# FPGA_-_POWER.net
KiCad netlist of a schematic drawn in Altium Designer
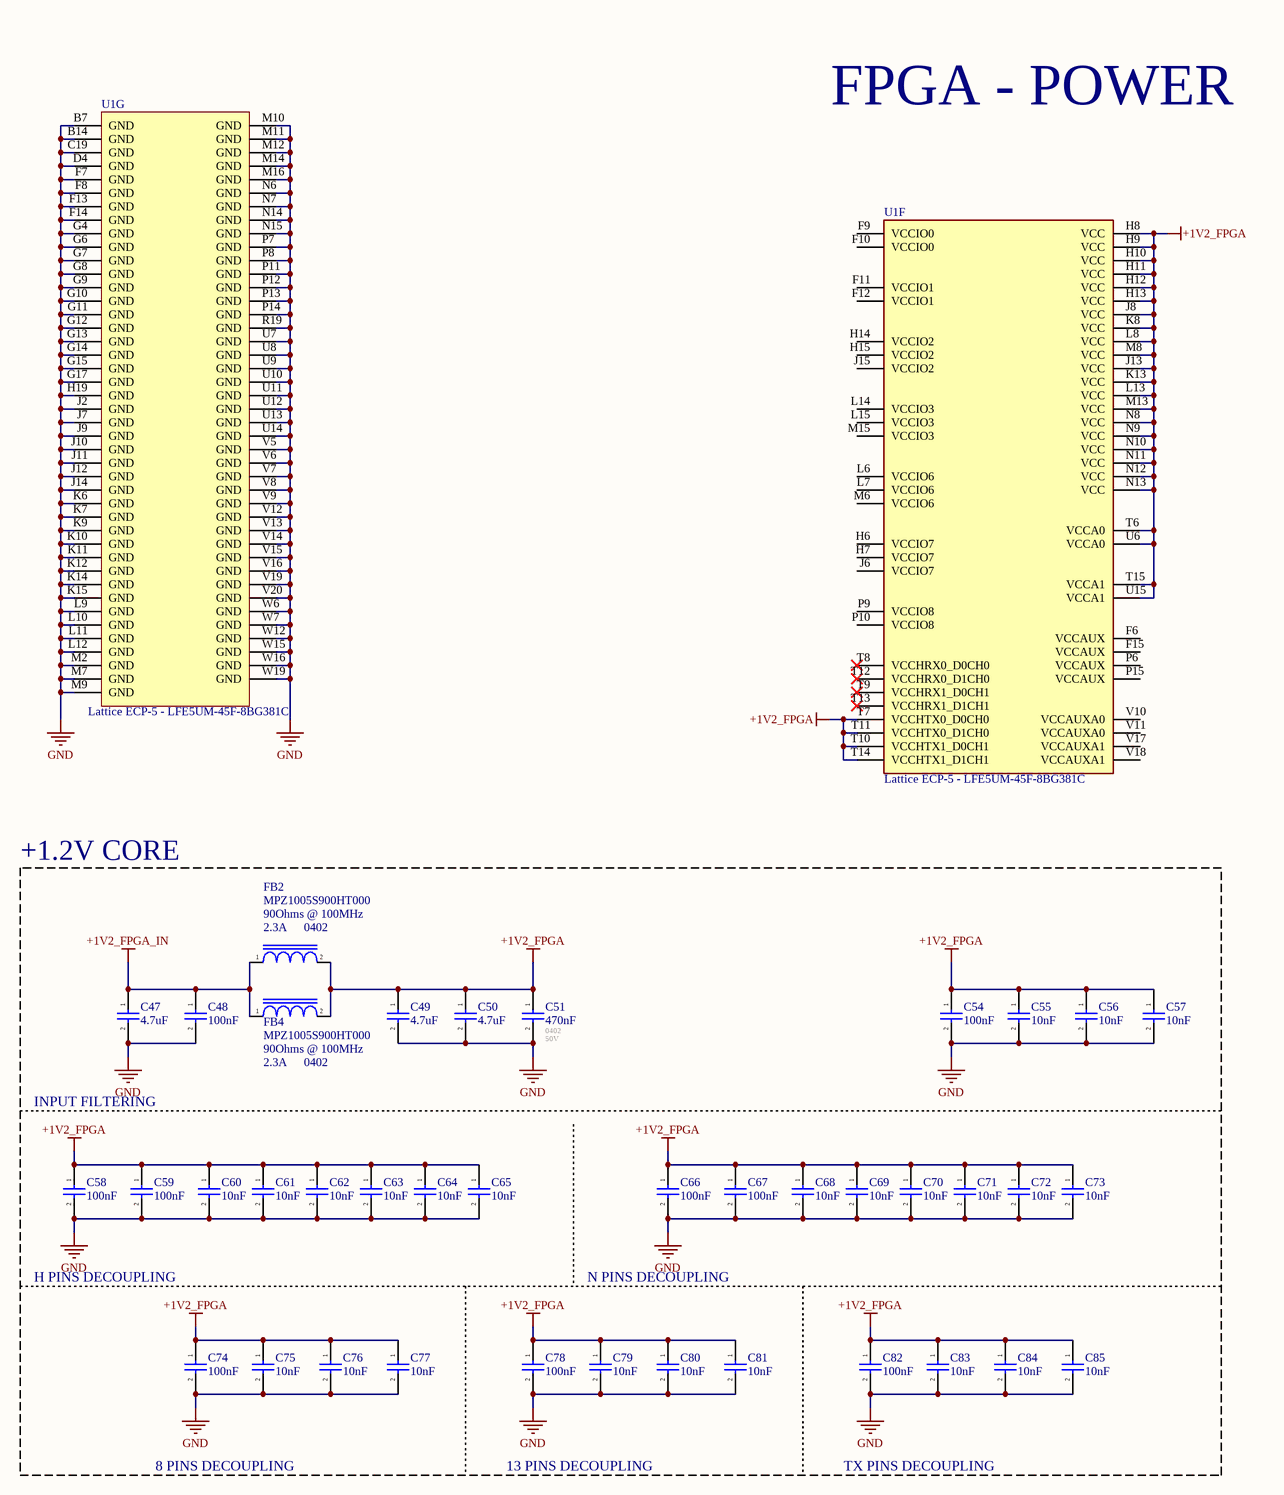
[diagram p0: FPGA - POWER.SchDoc]

(export (version "E")
  (design (tool "Eeschema 10.0.6"))
  (components
    (comp (ref "C47")
      (value "4.7uF")
      (footprint "CAP_0805")
      (description "Generic SMT Ceramic Capacitor")
      (libsource (lib "Symbols") (part "CAP_CER"))
    )
    (comp (ref "C48")
      (value "100nF")
      (footprint "CAP_0402")
      (description "Generic SMT Ceramic Capacitor")
      (libsource (lib "Symbols") (part "CAP_CER"))
    )
    (comp (ref "C49")
      (value "4.7uF")
      (footprint "CAP_0805")
      (description "Generic SMT Ceramic Capacitor")
      (libsource (lib "Symbols") (part "CAP_CER"))
    )
    (comp (ref "C50")
      (value "4.7uF")
      (footprint "CAP_0805")
      (description "Generic SMT Ceramic Capacitor")
      (libsource (lib "Symbols") (part "CAP_CER"))
    )
    (comp (ref "C51")
      (value "470nF")
      (footprint "0402")
      (description "Generic SMT Ceramic Capacitor")
      (fields (field (name "VOLTAGE - RATED") "50V"))
      (libsource (lib "Symbols") (part "CAP_CER"))
    )
    (comp (ref "C54")
      (value "100nF")
      (footprint "CAP_0402")
      (description "Generic SMT Ceramic Capacitor")
      (libsource (lib "Symbols") (part "CAP_CER"))
    )
    (comp (ref "C55")
      (value "10nF")
      (footprint "CAP_0201")
      (description "Generic SMT Ceramic Capacitor")
      (libsource (lib "Symbols") (part "CAP_CER"))
    )
    (comp (ref "C56")
      (value "10nF")
      (footprint "CAP_0201")
      (description "Generic SMT Ceramic Capacitor")
      (libsource (lib "Symbols") (part "CAP_CER"))
    )
    (comp (ref "C57")
      (value "10nF")
      (footprint "CAP_0201")
      (description "Generic SMT Ceramic Capacitor")
      (libsource (lib "Symbols") (part "CAP_CER"))
    )
    (comp (ref "C58")
      (value "100nF")
      (footprint "CAP_0402")
      (description "Generic SMT Ceramic Capacitor")
      (libsource (lib "Symbols") (part "CAP_CER"))
    )
    (comp (ref "C59")
      (value "100nF")
      (footprint "CAP_0402")
      (description "Generic SMT Ceramic Capacitor")
      (libsource (lib "Symbols") (part "CAP_CER"))
    )
    (comp (ref "C60")
      (value "10nF")
      (footprint "CAP_0201")
      (description "Generic SMT Ceramic Capacitor")
      (libsource (lib "Symbols") (part "CAP_CER"))
    )
    (comp (ref "C61")
      (value "10nF")
      (footprint "CAP_0201")
      (description "Generic SMT Ceramic Capacitor")
      (libsource (lib "Symbols") (part "CAP_CER"))
    )
    (comp (ref "C62")
      (value "10nF")
      (footprint "CAP_0201")
      (description "Generic SMT Ceramic Capacitor")
      (libsource (lib "Symbols") (part "CAP_CER"))
    )
    (comp (ref "C63")
      (value "10nF")
      (footprint "CAP_0201")
      (description "Generic SMT Ceramic Capacitor")
      (libsource (lib "Symbols") (part "CAP_CER"))
    )
    (comp (ref "C64")
      (value "10nF")
      (footprint "CAP_0201")
      (description "Generic SMT Ceramic Capacitor")
      (libsource (lib "Symbols") (part "CAP_CER"))
    )
    (comp (ref "C65")
      (value "10nF")
      (footprint "CAP_0201")
      (description "Generic SMT Ceramic Capacitor")
      (libsource (lib "Symbols") (part "CAP_CER"))
    )
    (comp (ref "C66")
      (value "100nF")
      (footprint "CAP_0402")
      (description "Generic SMT Ceramic Capacitor")
      (libsource (lib "Symbols") (part "CAP_CER"))
    )
    (comp (ref "C67")
      (value "100nF")
      (footprint "CAP_0402")
      (description "Generic SMT Ceramic Capacitor")
      (libsource (lib "Symbols") (part "CAP_CER"))
    )
    (comp (ref "C68")
      (value "10nF")
      (footprint "CAP_0201")
      (description "Generic SMT Ceramic Capacitor")
      (libsource (lib "Symbols") (part "CAP_CER"))
    )
    (comp (ref "C69")
      (value "10nF")
      (footprint "CAP_0201")
      (description "Generic SMT Ceramic Capacitor")
      (libsource (lib "Symbols") (part "CAP_CER"))
    )
    (comp (ref "C70")
      (value "10nF")
      (footprint "CAP_0201")
      (description "Generic SMT Ceramic Capacitor")
      (libsource (lib "Symbols") (part "CAP_CER"))
    )
    (comp (ref "C71")
      (value "10nF")
      (footprint "CAP_0201")
      (description "Generic SMT Ceramic Capacitor")
      (libsource (lib "Symbols") (part "CAP_CER"))
    )
    (comp (ref "C72")
      (value "10nF")
      (footprint "CAP_0201")
      (description "Generic SMT Ceramic Capacitor")
      (libsource (lib "Symbols") (part "CAP_CER"))
    )
    (comp (ref "C73")
      (value "10nF")
      (footprint "CAP_0201")
      (description "Generic SMT Ceramic Capacitor")
      (libsource (lib "Symbols") (part "CAP_CER"))
    )
    (comp (ref "C74")
      (value "100nF")
      (footprint "CAP_0402")
      (description "Generic SMT Ceramic Capacitor")
      (libsource (lib "Symbols") (part "CAP_CER"))
    )
    (comp (ref "C75")
      (value "10nF")
      (footprint "CAP_0201")
      (description "Generic SMT Ceramic Capacitor")
      (libsource (lib "Symbols") (part "CAP_CER"))
    )
    (comp (ref "C76")
      (value "10nF")
      (footprint "CAP_0201")
      (description "Generic SMT Ceramic Capacitor")
      (libsource (lib "Symbols") (part "CAP_CER"))
    )
    (comp (ref "C77")
      (value "10nF")
      (footprint "CAP_0201")
      (description "Generic SMT Ceramic Capacitor")
      (libsource (lib "Symbols") (part "CAP_CER"))
    )
    (comp (ref "C78")
      (value "100nF")
      (footprint "CAP_0402")
      (description "Generic SMT Ceramic Capacitor")
      (libsource (lib "Symbols") (part "CAP_CER"))
    )
    (comp (ref "C79")
      (value "10nF")
      (footprint "CAP_0201")
      (description "Generic SMT Ceramic Capacitor")
      (libsource (lib "Symbols") (part "CAP_CER"))
    )
    (comp (ref "C80")
      (value "10nF")
      (footprint "CAP_0201")
      (description "Generic SMT Ceramic Capacitor")
      (libsource (lib "Symbols") (part "CAP_CER"))
    )
    (comp (ref "C81")
      (value "10nF")
      (footprint "CAP_0201")
      (description "Generic SMT Ceramic Capacitor")
      (libsource (lib "Symbols") (part "CAP_CER"))
    )
    (comp (ref "C82")
      (value "100nF")
      (footprint "CAP_0402")
      (description "Generic SMT Ceramic Capacitor")
      (libsource (lib "Symbols") (part "CAP_CER"))
    )
    (comp (ref "C83")
      (value "10nF")
      (footprint "CAP_0201")
      (description "Generic SMT Ceramic Capacitor")
      (libsource (lib "Symbols") (part "CAP_CER"))
    )
    (comp (ref "C84")
      (value "10nF")
      (footprint "CAP_0201")
      (description "Generic SMT Ceramic Capacitor")
      (libsource (lib "Symbols") (part "CAP_CER"))
    )
    (comp (ref "C85")
      (value "10nF")
      (footprint "CAP_0201")
      (description "Generic SMT Ceramic Capacitor")
      (libsource (lib "Symbols") (part "CAP_CER"))
    )
    (comp (ref "FB2")
      (value "MPZ1005S900HT000")
      (footprint "IND_0402")
      (description "90 Ohms @ 100 MHz 1 Power Line Ferrite Bead 0402 (1005 Metric) 2.3A 38mOhm")
      (fields
        (field (name "IMPEDANCE @ FREQ") "90Ohms @ 100MHz")
        (field (name "PACKAGE / CASE") "0402")
        (field (name "CURRENT RATING") "2.3A")
      )
      (libsource (lib "CryptLib") (part "IND_MPZ1005S900HT000"))
    )
    (comp (ref "FB4")
      (value "MPZ1005S900HT000")
      (footprint "IND_0402")
      (description "90 Ohms @ 100 MHz 1 Power Line Ferrite Bead 0402 (1005 Metric) 2.3A 38mOhm")
      (fields
        (field (name "IMPEDANCE @ FREQ") "90Ohms @ 100MHz")
        (field (name "PACKAGE / CASE") "0402")
        (field (name "CURRENT RATING") "2.3A")
      )
      (libsource (lib "CryptLib") (part "IND_MPZ1005S900HT000"))
    )
    (comp (ref "U1")
      (value "Lattice ECP-5 - LFE5UM-45F-8BG381C")
      (footprint "CABGA-381")
      (description "IC FPGA 203 I/O 381CABGA")
      (fields (field (name "MFR") "Lattice Semiconductors"))
      (libsource (lib "CryptLib") (part "IC_LFE5UM-45F-8BG381C"))
    )
  )
  (nets
    (net (code "1") (name "+1V2_FPGA") (class "Default")
      (node (ref "C49") (pin "1") (pinfunction "1_1") (pintype "passive"))
      (node (ref "C50") (pin "1") (pinfunction "1_1") (pintype "passive"))
      (node (ref "C51") (pin "1") (pinfunction "1_1") (pintype "passive"))
      (node (ref "C54") (pin "1") (pinfunction "1_1") (pintype "passive"))
      (node (ref "C55") (pin "1") (pinfunction "1_1") (pintype "passive"))
      (node (ref "C56") (pin "1") (pinfunction "1_1") (pintype "passive"))
      (node (ref "C57") (pin "1") (pinfunction "1_1") (pintype "passive"))
      (node (ref "C58") (pin "1") (pinfunction "1_1") (pintype "passive"))
      (node (ref "C59") (pin "1") (pinfunction "1_1") (pintype "passive"))
      (node (ref "C60") (pin "1") (pinfunction "1_1") (pintype "passive"))
      (node (ref "C61") (pin "1") (pinfunction "1_1") (pintype "passive"))
      (node (ref "C62") (pin "1") (pinfunction "1_1") (pintype "passive"))
      (node (ref "C63") (pin "1") (pinfunction "1_1") (pintype "passive"))
      (node (ref "C64") (pin "1") (pinfunction "1_1") (pintype "passive"))
      (node (ref "C65") (pin "1") (pinfunction "1_1") (pintype "passive"))
      (node (ref "C66") (pin "1") (pinfunction "1_1") (pintype "passive"))
      (node (ref "C67") (pin "1") (pinfunction "1_1") (pintype "passive"))
      (node (ref "C68") (pin "1") (pinfunction "1_1") (pintype "passive"))
      (node (ref "C69") (pin "1") (pinfunction "1_1") (pintype "passive"))
      (node (ref "C70") (pin "1") (pinfunction "1_1") (pintype "passive"))
      (node (ref "C71") (pin "1") (pinfunction "1_1") (pintype "passive"))
      (node (ref "C72") (pin "1") (pinfunction "1_1") (pintype "passive"))
      (node (ref "C73") (pin "1") (pinfunction "1_1") (pintype "passive"))
      (node (ref "C74") (pin "1") (pinfunction "1_1") (pintype "passive"))
      (node (ref "C75") (pin "1") (pinfunction "1_1") (pintype "passive"))
      (node (ref "C76") (pin "1") (pinfunction "1_1") (pintype "passive"))
      (node (ref "C77") (pin "1") (pinfunction "1_1") (pintype "passive"))
      (node (ref "C78") (pin "1") (pinfunction "1_1") (pintype "passive"))
      (node (ref "C79") (pin "1") (pinfunction "1_1") (pintype "passive"))
      (node (ref "C80") (pin "1") (pinfunction "1_1") (pintype "passive"))
      (node (ref "C81") (pin "1") (pinfunction "1_1") (pintype "passive"))
      (node (ref "C82") (pin "1") (pinfunction "1_1") (pintype "passive"))
      (node (ref "C83") (pin "1") (pinfunction "1_1") (pintype "passive"))
      (node (ref "C84") (pin "1") (pinfunction "1_1") (pintype "passive"))
      (node (ref "C85") (pin "1") (pinfunction "1_1") (pintype "passive"))
      (node (ref "FB2") (pin "2") (pinfunction "2_2") (pintype "passive"))
      (node (ref "FB4") (pin "2") (pinfunction "2_2") (pintype "passive"))
      (node (ref "U1") (pin "H10") (pinfunction "VCC_H10") (pintype "power_in"))
      (node (ref "U1") (pin "H11") (pinfunction "VCC_H11") (pintype "power_in"))
      (node (ref "U1") (pin "H12") (pinfunction "VCC_H12") (pintype "power_in"))
      (node (ref "U1") (pin "H13") (pinfunction "VCC_H13") (pintype "power_in"))
      (node (ref "U1") (pin "H8") (pinfunction "VCC_H8") (pintype "power_in"))
      (node (ref "U1") (pin "H9") (pinfunction "VCC_H9") (pintype "power_in"))
      (node (ref "U1") (pin "J13") (pinfunction "VCC_J13") (pintype "power_in"))
      (node (ref "U1") (pin "J8") (pinfunction "VCC_J8") (pintype "power_in"))
      (node (ref "U1") (pin "K13") (pinfunction "VCC_K13") (pintype "power_in"))
      (node (ref "U1") (pin "K8") (pinfunction "VCC_K8") (pintype "power_in"))
      (node (ref "U1") (pin "L13") (pinfunction "VCC_L13") (pintype "power_in"))
      (node (ref "U1") (pin "L8") (pinfunction "VCC_L8") (pintype "power_in"))
      (node (ref "U1") (pin "M13") (pinfunction "VCC_M13") (pintype "power_in"))
      (node (ref "U1") (pin "M8") (pinfunction "VCC_M8") (pintype "power_in"))
      (node (ref "U1") (pin "N10") (pinfunction "VCC_N10") (pintype "power_in"))
      (node (ref "U1") (pin "N11") (pinfunction "VCC_N11") (pintype "power_in"))
      (node (ref "U1") (pin "N12") (pinfunction "VCC_N12") (pintype "power_in"))
      (node (ref "U1") (pin "N13") (pinfunction "VCC_N13") (pintype "power_in"))
      (node (ref "U1") (pin "N8") (pinfunction "VCC_N8") (pintype "power_in"))
      (node (ref "U1") (pin "N9") (pinfunction "VCC_N9") (pintype "power_in"))
      (node (ref "U1") (pin "T10") (pinfunction "VCCHTX1_D0CH1_T10") (pintype "power_in"))
      (node (ref "U1") (pin "T11") (pinfunction "VCCHTX0_D1CH0_T11") (pintype "power_in"))
      (node (ref "U1") (pin "T14") (pinfunction "VCCHTX1_D1CH1_T14") (pintype "power_in"))
      (node (ref "U1") (pin "T15") (pinfunction "VCCA1_T15") (pintype "power_in"))
      (node (ref "U1") (pin "T6") (pinfunction "VCCA0_T6") (pintype "power_in"))
      (node (ref "U1") (pin "T7") (pinfunction "VCCHTX0_D0CH0_T7") (pintype "power_in"))
      (node (ref "U1") (pin "U15") (pinfunction "VCCA1_U15") (pintype "power_in"))
      (node (ref "U1") (pin "U6") (pinfunction "VCCA0_U6") (pintype "power_in"))
    )
    (net (code "2") (name "+1V2_FPGA_IN") (class "Default")
      (node (ref "C47") (pin "1") (pinfunction "1_1") (pintype "passive"))
      (node (ref "C48") (pin "1") (pinfunction "1_1") (pintype "passive"))
      (node (ref "FB2") (pin "1") (pinfunction "1_1") (pintype "passive"))
      (node (ref "FB4") (pin "1") (pinfunction "1_1") (pintype "passive"))
    )
    (net (code "3") (name "GND") (class "Default")
      (node (ref "C47") (pin "2") (pinfunction "2_2") (pintype "passive"))
      (node (ref "C48") (pin "2") (pinfunction "2_2") (pintype "passive"))
      (node (ref "C49") (pin "2") (pinfunction "2_2") (pintype "passive"))
      (node (ref "C50") (pin "2") (pinfunction "2_2") (pintype "passive"))
      (node (ref "C51") (pin "2") (pinfunction "2_2") (pintype "passive"))
      (node (ref "C54") (pin "2") (pinfunction "2_2") (pintype "passive"))
      (node (ref "C55") (pin "2") (pinfunction "2_2") (pintype "passive"))
      (node (ref "C56") (pin "2") (pinfunction "2_2") (pintype "passive"))
      (node (ref "C57") (pin "2") (pinfunction "2_2") (pintype "passive"))
      (node (ref "C58") (pin "2") (pinfunction "2_2") (pintype "passive"))
      (node (ref "C59") (pin "2") (pinfunction "2_2") (pintype "passive"))
      (node (ref "C60") (pin "2") (pinfunction "2_2") (pintype "passive"))
      (node (ref "C61") (pin "2") (pinfunction "2_2") (pintype "passive"))
      (node (ref "C62") (pin "2") (pinfunction "2_2") (pintype "passive"))
      (node (ref "C63") (pin "2") (pinfunction "2_2") (pintype "passive"))
      (node (ref "C64") (pin "2") (pinfunction "2_2") (pintype "passive"))
      (node (ref "C65") (pin "2") (pinfunction "2_2") (pintype "passive"))
      (node (ref "C66") (pin "2") (pinfunction "2_2") (pintype "passive"))
      (node (ref "C67") (pin "2") (pinfunction "2_2") (pintype "passive"))
      (node (ref "C68") (pin "2") (pinfunction "2_2") (pintype "passive"))
      (node (ref "C69") (pin "2") (pinfunction "2_2") (pintype "passive"))
      (node (ref "C70") (pin "2") (pinfunction "2_2") (pintype "passive"))
      (node (ref "C71") (pin "2") (pinfunction "2_2") (pintype "passive"))
      (node (ref "C72") (pin "2") (pinfunction "2_2") (pintype "passive"))
      (node (ref "C73") (pin "2") (pinfunction "2_2") (pintype "passive"))
      (node (ref "C74") (pin "2") (pinfunction "2_2") (pintype "passive"))
      (node (ref "C75") (pin "2") (pinfunction "2_2") (pintype "passive"))
      (node (ref "C76") (pin "2") (pinfunction "2_2") (pintype "passive"))
      (node (ref "C77") (pin "2") (pinfunction "2_2") (pintype "passive"))
      (node (ref "C78") (pin "2") (pinfunction "2_2") (pintype "passive"))
      (node (ref "C79") (pin "2") (pinfunction "2_2") (pintype "passive"))
      (node (ref "C80") (pin "2") (pinfunction "2_2") (pintype "passive"))
      (node (ref "C81") (pin "2") (pinfunction "2_2") (pintype "passive"))
      (node (ref "C82") (pin "2") (pinfunction "2_2") (pintype "passive"))
      (node (ref "C83") (pin "2") (pinfunction "2_2") (pintype "passive"))
      (node (ref "C84") (pin "2") (pinfunction "2_2") (pintype "passive"))
      (node (ref "C85") (pin "2") (pinfunction "2_2") (pintype "passive"))
      (node (ref "U1") (pin "B14") (pinfunction "GND_B14") (pintype "power_in"))
      (node (ref "U1") (pin "B7") (pinfunction "GND_B7") (pintype "power_in"))
      (node (ref "U1") (pin "C19") (pinfunction "GND_C19") (pintype "power_in"))
      (node (ref "U1") (pin "D4") (pinfunction "GND_D4") (pintype "power_in"))
      (node (ref "U1") (pin "F13") (pinfunction "GND_F13") (pintype "power_in"))
      (node (ref "U1") (pin "F14") (pinfunction "GND_F14") (pintype "power_in"))
      (node (ref "U1") (pin "F7") (pinfunction "GND_F7") (pintype "power_in"))
      (node (ref "U1") (pin "F8") (pinfunction "GND_F8") (pintype "power_in"))
      (node (ref "U1") (pin "G10") (pinfunction "GND_G10") (pintype "power_in"))
      (node (ref "U1") (pin "G11") (pinfunction "GND_G11") (pintype "power_in"))
      (node (ref "U1") (pin "G12") (pinfunction "GND_G12") (pintype "power_in"))
      (node (ref "U1") (pin "G13") (pinfunction "GND_G13") (pintype "power_in"))
      (node (ref "U1") (pin "G14") (pinfunction "GND_G14") (pintype "power_in"))
      (node (ref "U1") (pin "G15") (pinfunction "GND_G15") (pintype "power_in"))
      (node (ref "U1") (pin "G17") (pinfunction "GND_G17") (pintype "power_in"))
      (node (ref "U1") (pin "G4") (pinfunction "GND_G4") (pintype "power_in"))
      (node (ref "U1") (pin "G6") (pinfunction "GND_G6") (pintype "power_in"))
      (node (ref "U1") (pin "G7") (pinfunction "GND_G7") (pintype "power_in"))
      (node (ref "U1") (pin "G8") (pinfunction "GND_G8") (pintype "power_in"))
      (node (ref "U1") (pin "G9") (pinfunction "GND_G9") (pintype "power_in"))
      (node (ref "U1") (pin "H19") (pinfunction "GND_H19") (pintype "power_in"))
      (node (ref "U1") (pin "J10") (pinfunction "GND_J10") (pintype "power_in"))
      (node (ref "U1") (pin "J11") (pinfunction "GND_J11") (pintype "power_in"))
      (node (ref "U1") (pin "J12") (pinfunction "GND_J12") (pintype "power_in"))
      (node (ref "U1") (pin "J14") (pinfunction "GND_J14") (pintype "power_in"))
      (node (ref "U1") (pin "J2") (pinfunction "GND_J2") (pintype "power_in"))
      (node (ref "U1") (pin "J7") (pinfunction "GND_J7") (pintype "power_in"))
      (node (ref "U1") (pin "J9") (pinfunction "GND_J9") (pintype "power_in"))
      (node (ref "U1") (pin "K10") (pinfunction "GND_K10") (pintype "power_in"))
      (node (ref "U1") (pin "K11") (pinfunction "GND_K11") (pintype "power_in"))
      (node (ref "U1") (pin "K12") (pinfunction "GND_K12") (pintype "power_in"))
      (node (ref "U1") (pin "K14") (pinfunction "GND_K14") (pintype "power_in"))
      (node (ref "U1") (pin "K15") (pinfunction "GND_K15") (pintype "power_in"))
      (node (ref "U1") (pin "K6") (pinfunction "GND_K6") (pintype "power_in"))
      (node (ref "U1") (pin "K7") (pinfunction "GND_K7") (pintype "power_in"))
      (node (ref "U1") (pin "K9") (pinfunction "GND_K9") (pintype "power_in"))
      (node (ref "U1") (pin "L10") (pinfunction "GND_L10") (pintype "power_in"))
      (node (ref "U1") (pin "L11") (pinfunction "GND_L11") (pintype "power_in"))
      (node (ref "U1") (pin "L12") (pinfunction "GND_L12") (pintype "power_in"))
      (node (ref "U1") (pin "L9") (pinfunction "GND_L9") (pintype "power_in"))
      (node (ref "U1") (pin "M10") (pinfunction "GND_M10") (pintype "power_in"))
      (node (ref "U1") (pin "M11") (pinfunction "GND_M11") (pintype "power_in"))
      (node (ref "U1") (pin "M12") (pinfunction "GND_M12") (pintype "power_in"))
      (node (ref "U1") (pin "M14") (pinfunction "GND_M14") (pintype "power_in"))
      (node (ref "U1") (pin "M16") (pinfunction "GND_M16") (pintype "power_in"))
      (node (ref "U1") (pin "M2") (pinfunction "GND_M2") (pintype "power_in"))
      (node (ref "U1") (pin "M7") (pinfunction "GND_M7") (pintype "power_in"))
      (node (ref "U1") (pin "M9") (pinfunction "GND_M9") (pintype "power_in"))
      (node (ref "U1") (pin "N14") (pinfunction "GND_N14") (pintype "power_in"))
      (node (ref "U1") (pin "N15") (pinfunction "GND_N15") (pintype "power_in"))
      (node (ref "U1") (pin "N6") (pinfunction "GND_N6") (pintype "power_in"))
      (node (ref "U1") (pin "N7") (pinfunction "GND_N7") (pintype "power_in"))
      (node (ref "U1") (pin "P11") (pinfunction "GND_P11") (pintype "power_in"))
      (node (ref "U1") (pin "P12") (pinfunction "GND_P12") (pintype "power_in"))
      (node (ref "U1") (pin "P13") (pinfunction "GND_P13") (pintype "power_in"))
      (node (ref "U1") (pin "P14") (pinfunction "GND_P14") (pintype "power_in"))
      (node (ref "U1") (pin "P7") (pinfunction "GND_P7") (pintype "power_in"))
      (node (ref "U1") (pin "P8") (pinfunction "GND_P8") (pintype "power_in"))
      (node (ref "U1") (pin "R19") (pinfunction "GND_R19") (pintype "power_in"))
      (node (ref "U1") (pin "U10") (pinfunction "GND_U10") (pintype "power_in"))
      (node (ref "U1") (pin "U11") (pinfunction "GND_U11") (pintype "power_in"))
      (node (ref "U1") (pin "U12") (pinfunction "GND_U12") (pintype "power_in"))
      (node (ref "U1") (pin "U13") (pinfunction "GND_U13") (pintype "power_in"))
      (node (ref "U1") (pin "U14") (pinfunction "GND_U14") (pintype "power_in"))
      (node (ref "U1") (pin "U7") (pinfunction "GND_U7") (pintype "power_in"))
      (node (ref "U1") (pin "U8") (pinfunction "GND_U8") (pintype "power_in"))
      (node (ref "U1") (pin "U9") (pinfunction "GND_U9") (pintype "power_in"))
      (node (ref "U1") (pin "V12") (pinfunction "GND_V12") (pintype "power_in"))
      (node (ref "U1") (pin "V13") (pinfunction "GND_V13") (pintype "power_in"))
      (node (ref "U1") (pin "V14") (pinfunction "GND_V14") (pintype "power_in"))
      (node (ref "U1") (pin "V15") (pinfunction "GND_V15") (pintype "power_in"))
      (node (ref "U1") (pin "V16") (pinfunction "GND_V16") (pintype "power_in"))
      (node (ref "U1") (pin "V19") (pinfunction "GND_V19") (pintype "power_in"))
      (node (ref "U1") (pin "V20") (pinfunction "GND_V20") (pintype "power_in"))
      (node (ref "U1") (pin "V5") (pinfunction "GND_V5") (pintype "power_in"))
      (node (ref "U1") (pin "V6") (pinfunction "GND_V6") (pintype "power_in"))
      (node (ref "U1") (pin "V7") (pinfunction "GND_V7") (pintype "power_in"))
      (node (ref "U1") (pin "V8") (pinfunction "GND_V8") (pintype "power_in"))
      (node (ref "U1") (pin "V9") (pinfunction "GND_V9") (pintype "power_in"))
      (node (ref "U1") (pin "W12") (pinfunction "GND_W12") (pintype "power_in"))
      (node (ref "U1") (pin "W15") (pinfunction "GND_W15") (pintype "power_in"))
      (node (ref "U1") (pin "W16") (pinfunction "GND_W16") (pintype "power_in"))
      (node (ref "U1") (pin "W19") (pinfunction "GND_W19") (pintype "power_in"))
      (node (ref "U1") (pin "W6") (pinfunction "GND_W6") (pintype "power_in"))
      (node (ref "U1") (pin "W7") (pinfunction "GND_W7") (pintype "power_in"))
    )
    (net (code "4") (name "unconnected-(U1F-VCCAUX-PadF6)") (class "Default")
      (node (ref "U1") (pin "F6") (pinfunction "VCCAUX_F6") (pintype "power_in"))
    )
    (net (code "5") (name "unconnected-(U1F-VCCAUX-PadF15)") (class "Default")
      (node (ref "U1") (pin "F15") (pinfunction "VCCAUX_F15") (pintype "power_in"))
    )
    (net (code "6") (name "unconnected-(U1F-VCCAUX-PadP6)") (class "Default")
      (node (ref "U1") (pin "P6") (pinfunction "VCCAUX_P6") (pintype "power_in"))
    )
    (net (code "7") (name "unconnected-(U1F-VCCAUX-PadP15)") (class "Default")
      (node (ref "U1") (pin "P15") (pinfunction "VCCAUX_P15") (pintype "power_in"))
    )
    (net (code "8") (name "unconnected-(U1F-VCCAUXA0-PadV10)") (class "Default")
      (node (ref "U1") (pin "V10") (pinfunction "VCCAUXA0_V10") (pintype "power_in"))
    )
    (net (code "9") (name "unconnected-(U1F-VCCAUXA0-PadV11)") (class "Default")
      (node (ref "U1") (pin "V11") (pinfunction "VCCAUXA0_V11") (pintype "power_in"))
    )
    (net (code "10") (name "unconnected-(U1F-VCCAUXA1-PadV17)") (class "Default")
      (node (ref "U1") (pin "V17") (pinfunction "VCCAUXA1_V17") (pintype "power_in"))
    )
    (net (code "11") (name "unconnected-(U1F-VCCAUXA1-PadV18)") (class "Default")
      (node (ref "U1") (pin "V18") (pinfunction "VCCAUXA1_V18") (pintype "power_in"))
    )
    (net (code "12") (name "unconnected-(U1F-VCCHRX0_D0CH0-PadT8)") (class "Default")
      (node (ref "U1") (pin "T8") (pinfunction "VCCHRX0_D0CH0_T8") (pintype "power_in+no_connect"))
    )
    (net (code "13") (name "unconnected-(U1F-VCCHRX0_D1CH0-PadT12)") (class "Default")
      (node (ref "U1") (pin "T12") (pinfunction "VCCHRX0_D1CH0_T12") (pintype "power_in+no_connect"))
    )
    (net (code "14") (name "unconnected-(U1F-VCCHRX1_D0CH1-PadT9)") (class "Default")
      (node (ref "U1") (pin "T9") (pinfunction "VCCHRX1_D0CH1_T9") (pintype "power_in+no_connect"))
    )
    (net (code "15") (name "unconnected-(U1F-VCCHRX1_D1CH1-PadT13)") (class "Default")
      (node (ref "U1") (pin "T13") (pinfunction "VCCHRX1_D1CH1_T13") (pintype "power_in+no_connect"))
    )
    (net (code "16") (name "unconnected-(U1F-VCCIO0-PadF9)") (class "Default")
      (node (ref "U1") (pin "F9") (pinfunction "VCCIO0_F9") (pintype "power_in"))
    )
    (net (code "17") (name "unconnected-(U1F-VCCIO0-PadF10)") (class "Default")
      (node (ref "U1") (pin "F10") (pinfunction "VCCIO0_F10") (pintype "power_in"))
    )
    (net (code "18") (name "unconnected-(U1F-VCCIO1-PadF11)") (class "Default")
      (node (ref "U1") (pin "F11") (pinfunction "VCCIO1_F11") (pintype "power_in"))
    )
    (net (code "19") (name "unconnected-(U1F-VCCIO1-PadF12)") (class "Default")
      (node (ref "U1") (pin "F12") (pinfunction "VCCIO1_F12") (pintype "power_in"))
    )
    (net (code "20") (name "unconnected-(U1F-VCCIO2-PadH14)") (class "Default")
      (node (ref "U1") (pin "H14") (pinfunction "VCCIO2_H14") (pintype "power_in"))
    )
    (net (code "21") (name "unconnected-(U1F-VCCIO2-PadH15)") (class "Default")
      (node (ref "U1") (pin "H15") (pinfunction "VCCIO2_H15") (pintype "power_in"))
    )
    (net (code "22") (name "unconnected-(U1F-VCCIO2-PadJ15)") (class "Default")
      (node (ref "U1") (pin "J15") (pinfunction "VCCIO2_J15") (pintype "power_in"))
    )
    (net (code "23") (name "unconnected-(U1F-VCCIO3-PadL14)") (class "Default")
      (node (ref "U1") (pin "L14") (pinfunction "VCCIO3_L14") (pintype "power_in"))
    )
    (net (code "24") (name "unconnected-(U1F-VCCIO3-PadL15)") (class "Default")
      (node (ref "U1") (pin "L15") (pinfunction "VCCIO3_L15") (pintype "power_in"))
    )
    (net (code "25") (name "unconnected-(U1F-VCCIO3-PadM15)") (class "Default")
      (node (ref "U1") (pin "M15") (pinfunction "VCCIO3_M15") (pintype "power_in"))
    )
    (net (code "26") (name "unconnected-(U1F-VCCIO6-PadL6)") (class "Default")
      (node (ref "U1") (pin "L6") (pinfunction "VCCIO6_L6") (pintype "power_in"))
    )
    (net (code "27") (name "unconnected-(U1F-VCCIO6-PadL7)") (class "Default")
      (node (ref "U1") (pin "L7") (pinfunction "VCCIO6_L7") (pintype "power_in"))
    )
    (net (code "28") (name "unconnected-(U1F-VCCIO6-PadM6)") (class "Default")
      (node (ref "U1") (pin "M6") (pinfunction "VCCIO6_M6") (pintype "power_in"))
    )
    (net (code "29") (name "unconnected-(U1F-VCCIO7-PadH6)") (class "Default")
      (node (ref "U1") (pin "H6") (pinfunction "VCCIO7_H6") (pintype "power_in"))
    )
    (net (code "30") (name "unconnected-(U1F-VCCIO7-PadH7)") (class "Default")
      (node (ref "U1") (pin "H7") (pinfunction "VCCIO7_H7") (pintype "power_in"))
    )
    (net (code "31") (name "unconnected-(U1F-VCCIO7-PadJ6)") (class "Default")
      (node (ref "U1") (pin "J6") (pinfunction "VCCIO7_J6") (pintype "power_in"))
    )
    (net (code "32") (name "unconnected-(U1F-VCCIO8-PadP9)") (class "Default")
      (node (ref "U1") (pin "P9") (pinfunction "VCCIO8_P9") (pintype "power_in"))
    )
    (net (code "33") (name "unconnected-(U1F-VCCIO8-PadP10)") (class "Default")
      (node (ref "U1") (pin "P10") (pinfunction "VCCIO8_P10") (pintype "power_in"))
    )
  )
)
